# SCH_pls_work_not_lose_2022-07-18.net
KiCad netlist of a schematic drawn in EasyEDA
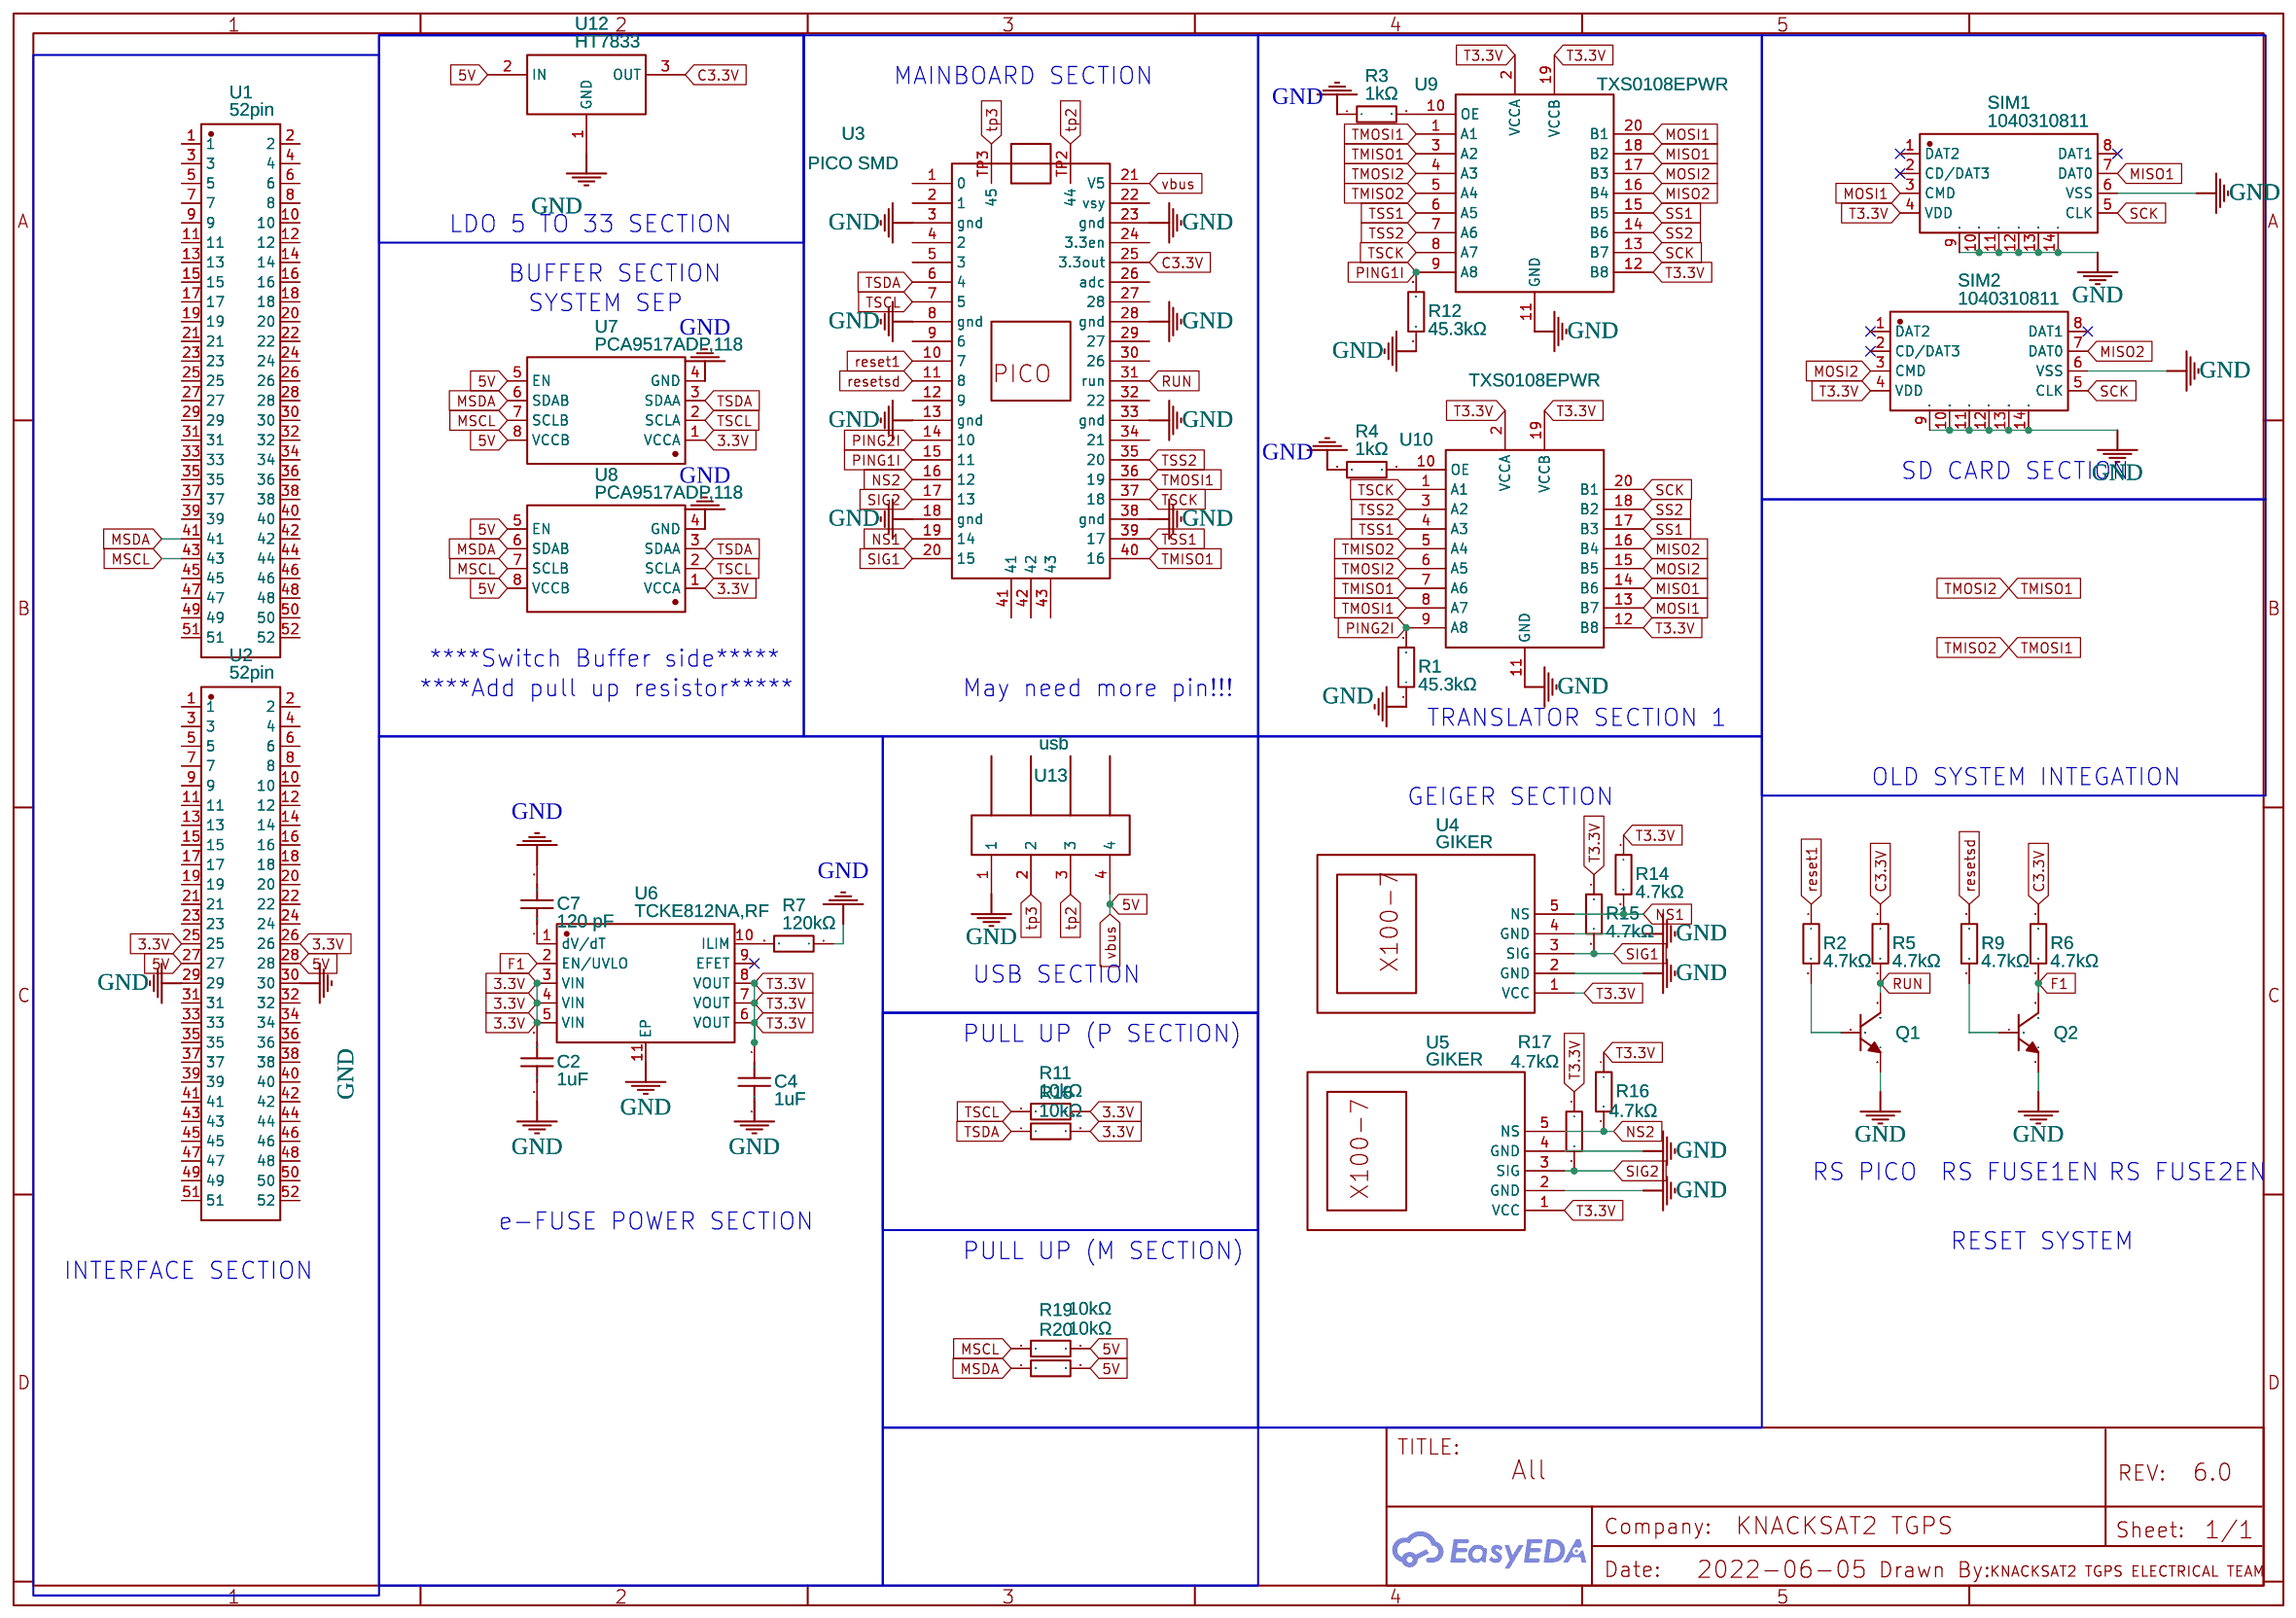
[diagram p0: schematic sheet]

(export (version "E")
  (design (tool "Eeschema 10.0.6"))
  (components
    (comp (ref "C2") (value "1uF") (libsource (lib "") (part "C_0603_US")))
    (comp (ref "C4") (value "1uF") (libsource (lib "") (part "C_0603_US")))
    (comp (ref "C7") (value "120 pF") (libsource (lib "") (part "C_0603_US")))
    (comp (ref "Q1")
      (value "2SC3324-BL(TE85L,F")
      (fields (field (name "BOM_Supplier Part") "C2999171"))
      (libsource (lib "") (part "2SC3324-BL(TE85L,F"))
    )
    (comp (ref "Q2")
      (value "2SC3324-BL(TE85L,F")
      (fields (field (name "BOM_Supplier Part") "C2999171"))
      (libsource (lib "") (part "2SC3324-BL(TE85L,F"))
    )
    (comp (ref "R1")
      (value "45.3kΩ")
      (fields
        (field (name "BOM_Manufacturer Part") "RMC040245.3K1%N")
        (field (name "BOM_Supplier Part") "C325554")
      )
      (libsource (lib "") (part "RMC040245.3K1%N"))
    )
    (comp (ref "R2")
      (value "4.7kΩ")
      (fields
        (field (name "BOM_Manufacturer Part") "RMC08054.7K1%N")
        (field (name "BOM_Supplier Part") "C269746")
      )
      (libsource (lib "") (part "RMC08054.7K1%N"))
    )
    (comp (ref "R3")
      (value "1kΩ")
      (fields
        (field (name "BOM_Manufacturer Part") "PTFR0805B1K00N9")
        (field (name "BOM_Supplier Part") "C328437")
      )
      (libsource (lib "") (part "PTFR0805B1K00N9"))
    )
    (comp (ref "R4")
      (value "1kΩ")
      (fields
        (field (name "BOM_Manufacturer Part") "PTFR0805B1K00N9")
        (field (name "BOM_Supplier Part") "C328437")
      )
      (libsource (lib "") (part "PTFR0805B1K00N9"))
    )
    (comp (ref "R5")
      (value "4.7kΩ")
      (fields
        (field (name "BOM_Manufacturer Part") "RMC08054.7K1%N")
        (field (name "BOM_Supplier Part") "C269746")
      )
      (libsource (lib "") (part "RMC08054.7K1%N"))
    )
    (comp (ref "R6")
      (value "4.7kΩ")
      (fields
        (field (name "BOM_Manufacturer Part") "RMC08054.7K1%N")
        (field (name "BOM_Supplier Part") "C269746")
      )
      (libsource (lib "") (part "RMC08054.7K1%N"))
    )
    (comp (ref "R7")
      (value "120kΩ")
      (fields
        (field (name "BOM_Manufacturer Part") "RMC0402120K1%N")
        (field (name "BOM_Supplier Part") "C325558")
      )
      (libsource (lib "") (part "RMC0402120K1%N"))
    )
    (comp (ref "R9")
      (value "4.7kΩ")
      (fields
        (field (name "BOM_Manufacturer Part") "RMC08054.7K1%N")
        (field (name "BOM_Supplier Part") "C269746")
      )
      (libsource (lib "") (part "RMC08054.7K1%N"))
    )
    (comp (ref "R11")
      (value "10kΩ")
      (fields
        (field (name "BOM_Manufacturer Part") "AECR0805F10K0K9")
        (field (name "BOM_Supplier Part") "C328381")
      )
      (libsource (lib "") (part "AECR0805F10K0K9"))
    )
    (comp (ref "R12")
      (value "45.3kΩ")
      (fields
        (field (name "BOM_Manufacturer Part") "RMC040245.3K1%N")
        (field (name "BOM_Supplier Part") "C325554")
      )
      (libsource (lib "") (part "RMC040245.3K1%N"))
    )
    (comp (ref "R14")
      (value "4.7kΩ")
      (fields
        (field (name "BOM_Manufacturer Part") "RMC08054.7K1%N")
        (field (name "BOM_Supplier Part") "C269746")
      )
      (libsource (lib "") (part "RMC08054.7K1%N"))
    )
    (comp (ref "R15")
      (value "4.7kΩ")
      (fields
        (field (name "BOM_Manufacturer Part") "RMC08054.7K1%N")
        (field (name "BOM_Supplier Part") "C269746")
      )
      (libsource (lib "") (part "RMC08054.7K1%N"))
    )
    (comp (ref "R16")
      (value "4.7kΩ")
      (fields
        (field (name "BOM_Manufacturer Part") "RMC08054.7K1%N")
        (field (name "BOM_Supplier Part") "C269746")
      )
      (libsource (lib "") (part "RMC08054.7K1%N"))
    )
    (comp (ref "R17")
      (value "4.7kΩ")
      (fields
        (field (name "BOM_Manufacturer Part") "RMC08054.7K1%N")
        (field (name "BOM_Supplier Part") "C269746")
      )
      (libsource (lib "") (part "RMC08054.7K1%N"))
    )
    (comp (ref "R18")
      (value "10kΩ")
      (fields
        (field (name "BOM_Manufacturer Part") "AECR0805F10K0K9")
        (field (name "BOM_Supplier Part") "C328381")
      )
      (libsource (lib "") (part "AECR0805F10K0K9"))
    )
    (comp (ref "R19")
      (value "10kΩ")
      (fields
        (field (name "BOM_Manufacturer Part") "AECR0805F10K0K9")
        (field (name "BOM_Supplier Part") "C328381")
      )
      (libsource (lib "") (part "AECR0805F10K0K9"))
    )
    (comp (ref "R20")
      (value "10kΩ")
      (fields
        (field (name "BOM_Manufacturer Part") "AECR0805F10K0K9")
        (field (name "BOM_Supplier Part") "C328381")
      )
      (libsource (lib "") (part "AECR0805F10K0K9"))
    )
    (comp (ref "SIM1")
      (value "1040310811")
      (fields (field (name "BOM_Supplier Part") "C585350"))
      (libsource (lib "") (part "1040310811"))
    )
    (comp (ref "SIM2")
      (value "1040310811")
      (fields (field (name "BOM_Supplier Part") "C585350"))
      (libsource (lib "") (part "1040310811"))
    )
    (comp (ref "U1") (value "52pin") (libsource (lib "") (part "52pin")))
    (comp (ref "U2") (value "52pin") (libsource (lib "") (part "52pin")))
    (comp (ref "U3") (value "PICO SMD") (libsource (lib "") (part "PICO SMD")))
    (comp (ref "U4") (value "GIKER") (libsource (lib "") (part "GIKER")))
    (comp (ref "U5") (value "GIKER") (libsource (lib "") (part "GIKER_1")))
    (comp (ref "U6")
      (value "TCKE812NA,RF")
      (fields (field (name "BOM_Supplier Part") "C1880271"))
      (libsource (lib "") (part "TCKE812NA,RF"))
    )
    (comp (ref "U7")
      (value "PCA9517ADP,118")
      (fields (field (name "BOM_Supplier Part") "C80799"))
      (libsource (lib "") (part "PCA9517ADP,118"))
    )
    (comp (ref "U8")
      (value "PCA9517ADP,118")
      (fields (field (name "BOM_Supplier Part") "C80799"))
      (libsource (lib "") (part "PCA9517ADP,118"))
    )
    (comp (ref "U9")
      (value "TXS0108EPWR")
      (fields (field (name "BOM_Supplier Part") "C17206"))
      (libsource (lib "") (part "TXS0108EPWR"))
    )
    (comp (ref "U10")
      (value "TXS0108EPWR")
      (fields (field (name "BOM_Supplier Part") "C17206"))
      (libsource (lib "") (part "TXS0108EPWR"))
    )
    (comp (ref "U12")
      (value "HT7833")
      (fields (field (name "BOM_Supplier Part") "C50936"))
      (libsource (lib "") (part "HT7833"))
    )
    (comp (ref "U13") (value "usb") (libsource (lib "") (part "usb")))
  )
  (nets
    (net (code "1") (name "3.3V") (class "Default")
      (node (ref "C2") (pin "2") (pinfunction "2_2") (pintype "unspecified"))
      (node (ref "R11") (pin "2") (pinfunction "2_2") (pintype "unspecified"))
      (node (ref "R18") (pin "2") (pinfunction "2_2") (pintype "unspecified"))
      (node (ref "U2") (pin "25") (pinfunction "25_25") (pintype "unspecified"))
      (node (ref "U2") (pin "26") (pinfunction "26_26") (pintype "unspecified"))
      (node (ref "U6") (pin "3") (pinfunction "VIN_3") (pintype "unspecified"))
      (node (ref "U6") (pin "4") (pinfunction "VIN_4") (pintype "unspecified"))
      (node (ref "U6") (pin "5") (pinfunction "VIN_5") (pintype "unspecified"))
      (node (ref "U7") (pin "1") (pinfunction "VCCA_1") (pintype "unspecified"))
      (node (ref "U8") (pin "1") (pinfunction "VCCA_1") (pintype "unspecified"))
    )
    (net (code "2") (name "5V") (class "Default")
      (node (ref "R19") (pin "2") (pinfunction "2_2") (pintype "unspecified"))
      (node (ref "R20") (pin "2") (pinfunction "2_2") (pintype "unspecified"))
      (node (ref "U12") (pin "2") (pinfunction "IN_2") (pintype "passive"))
      (node (ref "U13") (pin "4") (pinfunction "4_4") (pintype "unspecified"))
      (node (ref "U2") (pin "27") (pinfunction "27_27") (pintype "unspecified"))
      (node (ref "U2") (pin "28") (pinfunction "28_28") (pintype "unspecified"))
      (node (ref "U3") (pin "21") (pinfunction "V5_21") (pintype "unspecified"))
      (node (ref "U7") (pin "5") (pinfunction "EN_5") (pintype "unspecified"))
      (node (ref "U7") (pin "8") (pinfunction "VCCB_8") (pintype "unspecified"))
      (node (ref "U8") (pin "5") (pinfunction "EN_5") (pintype "unspecified"))
      (node (ref "U8") (pin "8") (pinfunction "VCCB_8") (pintype "unspecified"))
    )
    (net (code "3") (name "C3.3V") (class "Default")
      (node (ref "R5") (pin "1") (pinfunction "1_1") (pintype "unspecified"))
      (node (ref "R6") (pin "1") (pinfunction "1_1") (pintype "unspecified"))
      (node (ref "U12") (pin "3") (pinfunction "OUT_3") (pintype "passive"))
      (node (ref "U3") (pin "25") (pinfunction "3.3out_25") (pintype "unspecified"))
    )
    (net (code "4") (name "F1") (class "Default")
      (node (ref "Q2") (pin "3") (pinfunction "C_3") (pintype "unspecified"))
      (node (ref "R6") (pin "2") (pinfunction "2_2") (pintype "unspecified"))
      (node (ref "U6") (pin "2") (pinfunction "EN/UVLO_2") (pintype "unspecified"))
    )
    (net (code "5") (name "GND") (class "Default")
      (node (ref "C2") (pin "1") (pinfunction "1_1") (pintype "unspecified"))
      (node (ref "C4") (pin "1") (pinfunction "1_1") (pintype "unspecified"))
      (node (ref "C7") (pin "2") (pinfunction "2_2") (pintype "unspecified"))
      (node (ref "Q1") (pin "2") (pinfunction "E_2") (pintype "unspecified"))
      (node (ref "Q2") (pin "2") (pinfunction "E_2") (pintype "unspecified"))
      (node (ref "R1") (pin "1") (pinfunction "1_1") (pintype "unspecified"))
      (node (ref "R12") (pin "1") (pinfunction "1_1") (pintype "unspecified"))
      (node (ref "R3") (pin "1") (pinfunction "1_1") (pintype "unspecified"))
      (node (ref "R4") (pin "1") (pinfunction "1_1") (pintype "unspecified"))
      (node (ref "R7") (pin "1") (pinfunction "1_1") (pintype "unspecified"))
      (node (ref "SIM1") (pin "10") (pinfunction "10_10") (pintype "unspecified"))
      (node (ref "SIM1") (pin "11") (pinfunction "11_11") (pintype "unspecified"))
      (node (ref "SIM1") (pin "12") (pinfunction "12_12") (pintype "unspecified"))
      (node (ref "SIM1") (pin "13") (pinfunction "13_13") (pintype "unspecified"))
      (node (ref "SIM1") (pin "14") (pinfunction "14_14") (pintype "unspecified"))
      (node (ref "SIM1") (pin "6") (pinfunction "VSS_6") (pintype "unspecified"))
      (node (ref "SIM1") (pin "9") (pinfunction "9_9") (pintype "unspecified"))
      (node (ref "SIM2") (pin "10") (pinfunction "10_10") (pintype "unspecified"))
      (node (ref "SIM2") (pin "11") (pinfunction "11_11") (pintype "unspecified"))
      (node (ref "SIM2") (pin "12") (pinfunction "12_12") (pintype "unspecified"))
      (node (ref "SIM2") (pin "13") (pinfunction "13_13") (pintype "unspecified"))
      (node (ref "SIM2") (pin "14") (pinfunction "14_14") (pintype "unspecified"))
      (node (ref "SIM2") (pin "6") (pinfunction "VSS_6") (pintype "unspecified"))
      (node (ref "SIM2") (pin "9") (pinfunction "9_9") (pintype "unspecified"))
      (node (ref "U10") (pin "11") (pinfunction "GND_11") (pintype "unspecified"))
      (node (ref "U12") (pin "1") (pinfunction "GND_1") (pintype "passive"))
      (node (ref "U13") (pin "1") (pinfunction "1_1") (pintype "unspecified"))
      (node (ref "U2") (pin "29") (pinfunction "29_29") (pintype "unspecified"))
      (node (ref "U2") (pin "30") (pinfunction "30_30") (pintype "unspecified"))
      (node (ref "U3") (pin "13") (pinfunction "gnd_13") (pintype "unspecified"))
      (node (ref "U3") (pin "18") (pinfunction "gnd_18") (pintype "unspecified"))
      (node (ref "U3") (pin "23") (pinfunction "gnd_23") (pintype "unspecified"))
      (node (ref "U3") (pin "28") (pinfunction "gnd_28") (pintype "unspecified"))
      (node (ref "U3") (pin "3") (pinfunction "gnd_3") (pintype "unspecified"))
      (node (ref "U3") (pin "33") (pinfunction "gnd_33") (pintype "unspecified"))
      (node (ref "U3") (pin "38") (pinfunction "gnd_38") (pintype "unspecified"))
      (node (ref "U3") (pin "8") (pinfunction "gnd_8") (pintype "unspecified"))
      (node (ref "U4") (pin "2") (pinfunction "GND_2") (pintype "unspecified"))
      (node (ref "U4") (pin "4") (pinfunction "GND_4") (pintype "unspecified"))
      (node (ref "U5") (pin "2") (pinfunction "GND_2") (pintype "unspecified"))
      (node (ref "U5") (pin "4") (pinfunction "GND_4") (pintype "unspecified"))
      (node (ref "U6") (pin "11") (pinfunction "EP_11") (pintype "unspecified"))
      (node (ref "U7") (pin "4") (pinfunction "GND_4") (pintype "unspecified"))
      (node (ref "U8") (pin "4") (pinfunction "GND_4") (pintype "unspecified"))
      (node (ref "U9") (pin "11") (pinfunction "GND_11") (pintype "unspecified"))
    )
    (net (code "6") (name "MISO1") (class "Default")
      (node (ref "SIM1") (pin "7") (pinfunction "DAT0_7") (pintype "unspecified"))
      (node (ref "U10") (pin "14") (pinfunction "B6_14") (pintype "unspecified"))
      (node (ref "U9") (pin "18") (pinfunction "B2_18") (pintype "unspecified"))
    )
    (net (code "7") (name "MISO2") (class "Default")
      (node (ref "SIM2") (pin "7") (pinfunction "DAT0_7") (pintype "unspecified"))
      (node (ref "U10") (pin "16") (pinfunction "B4_16") (pintype "unspecified"))
      (node (ref "U9") (pin "16") (pinfunction "B4_16") (pintype "unspecified"))
    )
    (net (code "8") (name "MOSI1") (class "Default")
      (node (ref "SIM1") (pin "3") (pinfunction "CMD_3") (pintype "unspecified"))
      (node (ref "U10") (pin "13") (pinfunction "B7_13") (pintype "unspecified"))
      (node (ref "U9") (pin "20") (pinfunction "B1_20") (pintype "unspecified"))
    )
    (net (code "9") (name "MOSI2") (class "Default")
      (node (ref "SIM2") (pin "3") (pinfunction "CMD_3") (pintype "unspecified"))
      (node (ref "U10") (pin "15") (pinfunction "B5_15") (pintype "unspecified"))
      (node (ref "U9") (pin "17") (pinfunction "B3_17") (pintype "unspecified"))
    )
    (net (code "10") (name "MSCL") (class "Default")
      (node (ref "R19") (pin "1") (pinfunction "1_1") (pintype "unspecified"))
      (node (ref "U1") (pin "43") (pinfunction "43_43") (pintype "unspecified"))
      (node (ref "U7") (pin "7") (pinfunction "SCLB_7") (pintype "unspecified"))
      (node (ref "U8") (pin "7") (pinfunction "SCLB_7") (pintype "unspecified"))
    )
    (net (code "11") (name "MSDA") (class "Default")
      (node (ref "R20") (pin "1") (pinfunction "1_1") (pintype "unspecified"))
      (node (ref "U1") (pin "41") (pinfunction "41_41") (pintype "unspecified"))
      (node (ref "U7") (pin "6") (pinfunction "SDAB_6") (pintype "unspecified"))
      (node (ref "U8") (pin "6") (pinfunction "SDAB_6") (pintype "unspecified"))
    )
    (net (code "12") (name "NS1") (class "Default")
      (node (ref "R14") (pin "2") (pinfunction "2_2") (pintype "unspecified"))
      (node (ref "U3") (pin "19") (pinfunction "14_19") (pintype "unspecified"))
      (node (ref "U4") (pin "5") (pinfunction "NS_5") (pintype "unspecified"))
    )
    (net (code "13") (name "NS2") (class "Default")
      (node (ref "R16") (pin "2") (pinfunction "2_2") (pintype "unspecified"))
      (node (ref "U3") (pin "16") (pinfunction "12_16") (pintype "unspecified"))
      (node (ref "U5") (pin "5") (pinfunction "NS_5") (pintype "unspecified"))
    )
    (net (code "14") (name "Net-(Q1-B)") (class "Default")
      (node (ref "Q1") (pin "1") (pinfunction "B_1") (pintype "unspecified"))
      (node (ref "R2") (pin "2") (pinfunction "2_2") (pintype "unspecified"))
    )
    (net (code "15") (name "Net-(Q2-B)") (class "Default")
      (node (ref "Q2") (pin "1") (pinfunction "B_1") (pintype "unspecified"))
      (node (ref "R9") (pin "2") (pinfunction "2_2") (pintype "unspecified"))
    )
    (net (code "16") (name "Net-(U6-ILIM)") (class "Default")
      (node (ref "R7") (pin "2") (pinfunction "2_2") (pintype "unspecified"))
      (node (ref "U6") (pin "10") (pinfunction "ILIM_10") (pintype "unspecified"))
    )
    (net (code "17") (name "Net-(U6-dV{slash}dT)") (class "Default")
      (node (ref "C7") (pin "1") (pinfunction "1_1") (pintype "unspecified"))
      (node (ref "U6") (pin "1") (pinfunction "dV/dT_1") (pintype "unspecified"))
    )
    (net (code "18") (name "Net-(U9-OE)") (class "Default")
      (node (ref "R3") (pin "2") (pinfunction "2_2") (pintype "unspecified"))
      (node (ref "U9") (pin "10") (pinfunction "OE_10") (pintype "unspecified"))
    )
    (net (code "19") (name "Net-(U10-OE)") (class "Default")
      (node (ref "R4") (pin "2") (pinfunction "2_2") (pintype "unspecified"))
      (node (ref "U10") (pin "10") (pinfunction "OE_10") (pintype "unspecified"))
    )
    (net (code "20") (name "PING1I") (class "Default")
      (node (ref "R12") (pin "2") (pinfunction "2_2") (pintype "unspecified"))
      (node (ref "U3") (pin "15") (pinfunction "11_15") (pintype "unspecified"))
      (node (ref "U9") (pin "9") (pinfunction "A8_9") (pintype "unspecified"))
    )
    (net (code "21") (name "PING2I") (class "Default")
      (node (ref "R1") (pin "2") (pinfunction "2_2") (pintype "unspecified"))
      (node (ref "U10") (pin "9") (pinfunction "A8_9") (pintype "unspecified"))
      (node (ref "U3") (pin "14") (pinfunction "10_14") (pintype "unspecified"))
    )
    (net (code "22") (name "RUN") (class "Default")
      (node (ref "Q1") (pin "3") (pinfunction "C_3") (pintype "unspecified"))
      (node (ref "R5") (pin "2") (pinfunction "2_2") (pintype "unspecified"))
      (node (ref "U3") (pin "31") (pinfunction "run_31") (pintype "unspecified"))
    )
    (net (code "23") (name "SCK") (class "Default")
      (node (ref "SIM1") (pin "5") (pinfunction "CLK_5") (pintype "unspecified"))
      (node (ref "SIM2") (pin "5") (pinfunction "CLK_5") (pintype "unspecified"))
      (node (ref "U10") (pin "20") (pinfunction "B1_20") (pintype "unspecified"))
      (node (ref "U9") (pin "13") (pinfunction "B7_13") (pintype "unspecified"))
    )
    (net (code "24") (name "SIG1") (class "Default")
      (node (ref "R15") (pin "2") (pinfunction "2_2") (pintype "unspecified"))
      (node (ref "U3") (pin "20") (pinfunction "15_20") (pintype "unspecified"))
      (node (ref "U4") (pin "3") (pinfunction "SIG_3") (pintype "unspecified"))
    )
    (net (code "25") (name "SIG2") (class "Default")
      (node (ref "R17") (pin "2") (pinfunction "2_2") (pintype "unspecified"))
      (node (ref "U3") (pin "17") (pinfunction "13_17") (pintype "unspecified"))
      (node (ref "U5") (pin "3") (pinfunction "SIG_3") (pintype "unspecified"))
    )
    (net (code "26") (name "SS1") (class "Default")
      (node (ref "U10") (pin "17") (pinfunction "B3_17") (pintype "unspecified"))
      (node (ref "U9") (pin "15") (pinfunction "B5_15") (pintype "unspecified"))
    )
    (net (code "27") (name "SS2") (class "Default")
      (node (ref "U10") (pin "18") (pinfunction "B2_18") (pintype "unspecified"))
      (node (ref "U9") (pin "14") (pinfunction "B6_14") (pintype "unspecified"))
    )
    (net (code "28") (name "T3.3V") (class "Default")
      (node (ref "C4") (pin "2") (pinfunction "2_2") (pintype "unspecified"))
      (node (ref "R14") (pin "1") (pinfunction "1_1") (pintype "unspecified"))
      (node (ref "R15") (pin "1") (pinfunction "1_1") (pintype "unspecified"))
      (node (ref "R16") (pin "1") (pinfunction "1_1") (pintype "unspecified"))
      (node (ref "R17") (pin "1") (pinfunction "1_1") (pintype "unspecified"))
      (node (ref "SIM1") (pin "4") (pinfunction "VDD_4") (pintype "unspecified"))
      (node (ref "SIM2") (pin "4") (pinfunction "VDD_4") (pintype "unspecified"))
      (node (ref "U10") (pin "12") (pinfunction "B8_12") (pintype "unspecified"))
      (node (ref "U10") (pin "19") (pinfunction "VCCB_19") (pintype "unspecified"))
      (node (ref "U10") (pin "2") (pinfunction "VCCA_2") (pintype "unspecified"))
      (node (ref "U4") (pin "1") (pinfunction "VCC_1") (pintype "unspecified"))
      (node (ref "U5") (pin "1") (pinfunction "VCC_1") (pintype "unspecified"))
      (node (ref "U6") (pin "6") (pinfunction "VOUT_6") (pintype "unspecified"))
      (node (ref "U6") (pin "7") (pinfunction "VOUT_7") (pintype "unspecified"))
      (node (ref "U6") (pin "8") (pinfunction "VOUT_8") (pintype "unspecified"))
      (node (ref "U9") (pin "12") (pinfunction "B8_12") (pintype "unspecified"))
      (node (ref "U9") (pin "19") (pinfunction "VCCB_19") (pintype "unspecified"))
      (node (ref "U9") (pin "2") (pinfunction "VCCA_2") (pintype "unspecified"))
    )
    (net (code "29") (name "TMISO1") (class "Default")
      (node (ref "U10") (pin "6") (pinfunction "A5_6") (pintype "unspecified"))
      (node (ref "U10") (pin "7") (pinfunction "A6_7") (pintype "unspecified"))
      (node (ref "U3") (pin "40") (pinfunction "16_40") (pintype "unspecified"))
      (node (ref "U9") (pin "3") (pinfunction "A2_3") (pintype "unspecified"))
      (node (ref "U9") (pin "4") (pinfunction "A3_4") (pintype "unspecified"))
    )
    (net (code "30") (name "TMISO2") (class "Default")
      (node (ref "U10") (pin "5") (pinfunction "A4_5") (pintype "unspecified"))
      (node (ref "U10") (pin "8") (pinfunction "A7_8") (pintype "unspecified"))
      (node (ref "U3") (pin "36") (pinfunction "19_36") (pintype "unspecified"))
      (node (ref "U9") (pin "1") (pinfunction "A1_1") (pintype "unspecified"))
      (node (ref "U9") (pin "5") (pinfunction "A4_5") (pintype "unspecified"))
    )
    (net (code "31") (name "TSCK") (class "Default")
      (node (ref "U10") (pin "1") (pinfunction "A1_1") (pintype "unspecified"))
      (node (ref "U3") (pin "37") (pinfunction "18_37") (pintype "unspecified"))
      (node (ref "U9") (pin "8") (pinfunction "A7_8") (pintype "unspecified"))
    )
    (net (code "32") (name "TSCL") (class "Default")
      (node (ref "R11") (pin "1") (pinfunction "1_1") (pintype "unspecified"))
      (node (ref "U3") (pin "7") (pinfunction "5_7") (pintype "unspecified"))
      (node (ref "U7") (pin "2") (pinfunction "SCLA_2") (pintype "unspecified"))
      (node (ref "U8") (pin "2") (pinfunction "SCLA_2") (pintype "unspecified"))
    )
    (net (code "33") (name "TSDA") (class "Default")
      (node (ref "R18") (pin "1") (pinfunction "1_1") (pintype "unspecified"))
      (node (ref "U3") (pin "6") (pinfunction "4_6") (pintype "unspecified"))
      (node (ref "U7") (pin "3") (pinfunction "SDAA_3") (pintype "unspecified"))
      (node (ref "U8") (pin "3") (pinfunction "SDAA_3") (pintype "unspecified"))
    )
    (net (code "34") (name "TSS1") (class "Default")
      (node (ref "U10") (pin "4") (pinfunction "A3_4") (pintype "unspecified"))
      (node (ref "U3") (pin "39") (pinfunction "17_39") (pintype "unspecified"))
      (node (ref "U9") (pin "6") (pinfunction "A5_6") (pintype "unspecified"))
    )
    (net (code "35") (name "TSS2") (class "Default")
      (node (ref "U10") (pin "3") (pinfunction "A2_3") (pintype "unspecified"))
      (node (ref "U3") (pin "35") (pinfunction "20_35") (pintype "unspecified"))
      (node (ref "U9") (pin "7") (pinfunction "A6_7") (pintype "unspecified"))
    )
    (net (code "36") (name "reset1") (class "Default")
      (node (ref "R2") (pin "1") (pinfunction "1_1") (pintype "unspecified"))
      (node (ref "U3") (pin "10") (pinfunction "7_10") (pintype "unspecified"))
    )
    (net (code "37") (name "resetsd") (class "Default")
      (node (ref "R9") (pin "1") (pinfunction "1_1") (pintype "unspecified"))
      (node (ref "U3") (pin "11") (pinfunction "8_11") (pintype "unspecified"))
    )
    (net (code "38") (name "tp2") (class "Default")
      (node (ref "U13") (pin "3") (pinfunction "3_3") (pintype "unspecified"))
      (node (ref "U3") (pin "TP2") (pinfunction "44_TP2") (pintype "unspecified"))
    )
    (net (code "39") (name "tp3") (class "Default")
      (node (ref "U13") (pin "2") (pinfunction "2_2") (pintype "unspecified"))
      (node (ref "U3") (pin "TP3") (pinfunction "45_TP3") (pintype "unspecified"))
    )
    (net (code "40") (name "unconnected-(SIM1-CD{slash}DAT3-Pad2)") (class "Default")
      (node (ref "SIM1") (pin "2") (pinfunction "CD/DAT3_2") (pintype "unspecified+no_connect"))
    )
    (net (code "41") (name "unconnected-(SIM1-DAT1-Pad8)") (class "Default")
      (node (ref "SIM1") (pin "8") (pinfunction "DAT1_8") (pintype "unspecified+no_connect"))
    )
    (net (code "42") (name "unconnected-(SIM1-DAT2-Pad1)") (class "Default")
      (node (ref "SIM1") (pin "1") (pinfunction "DAT2_1") (pintype "unspecified+no_connect"))
    )
    (net (code "43") (name "unconnected-(SIM2-CD{slash}DAT3-Pad2)") (class "Default")
      (node (ref "SIM2") (pin "2") (pinfunction "CD/DAT3_2") (pintype "unspecified+no_connect"))
    )
    (net (code "44") (name "unconnected-(SIM2-DAT1-Pad8)") (class "Default")
      (node (ref "SIM2") (pin "8") (pinfunction "DAT1_8") (pintype "unspecified+no_connect"))
    )
    (net (code "45") (name "unconnected-(SIM2-DAT2-Pad1)") (class "Default")
      (node (ref "SIM2") (pin "1") (pinfunction "DAT2_1") (pintype "unspecified+no_connect"))
    )
    (net (code "46") (name "unconnected-(U1-Pad1)") (class "Default")
      (node (ref "U1") (pin "1") (pinfunction "1_1") (pintype "unspecified"))
    )
    (net (code "47") (name "unconnected-(U1-Pad2)") (class "Default")
      (node (ref "U1") (pin "2") (pinfunction "2_2") (pintype "unspecified"))
    )
    (net (code "48") (name "unconnected-(U1-Pad3)") (class "Default")
      (node (ref "U1") (pin "3") (pinfunction "3_3") (pintype "unspecified"))
    )
    (net (code "49") (name "unconnected-(U1-Pad4)") (class "Default")
      (node (ref "U1") (pin "4") (pinfunction "4_4") (pintype "unspecified"))
    )
    (net (code "50") (name "unconnected-(U1-Pad5)") (class "Default")
      (node (ref "U1") (pin "5") (pinfunction "5_5") (pintype "unspecified"))
    )
    (net (code "51") (name "unconnected-(U1-Pad6)") (class "Default")
      (node (ref "U1") (pin "6") (pinfunction "6_6") (pintype "unspecified"))
    )
    (net (code "52") (name "unconnected-(U1-Pad7)") (class "Default")
      (node (ref "U1") (pin "7") (pinfunction "7_7") (pintype "unspecified"))
    )
    (net (code "53") (name "unconnected-(U1-Pad8)") (class "Default")
      (node (ref "U1") (pin "8") (pinfunction "8_8") (pintype "unspecified"))
    )
    (net (code "54") (name "unconnected-(U1-Pad9)") (class "Default")
      (node (ref "U1") (pin "9") (pinfunction "9_9") (pintype "unspecified"))
    )
    (net (code "55") (name "unconnected-(U1-Pad10)") (class "Default")
      (node (ref "U1") (pin "10") (pinfunction "10_10") (pintype "unspecified"))
    )
    (net (code "56") (name "unconnected-(U1-Pad11)") (class "Default")
      (node (ref "U1") (pin "11") (pinfunction "11_11") (pintype "unspecified"))
    )
    (net (code "57") (name "unconnected-(U1-Pad12)") (class "Default")
      (node (ref "U1") (pin "12") (pinfunction "12_12") (pintype "unspecified"))
    )
    (net (code "58") (name "unconnected-(U1-Pad13)") (class "Default")
      (node (ref "U1") (pin "13") (pinfunction "13_13") (pintype "unspecified"))
    )
    (net (code "59") (name "unconnected-(U1-Pad14)") (class "Default")
      (node (ref "U1") (pin "14") (pinfunction "14_14") (pintype "unspecified"))
    )
    (net (code "60") (name "unconnected-(U1-Pad15)") (class "Default")
      (node (ref "U1") (pin "15") (pinfunction "15_15") (pintype "unspecified"))
    )
    (net (code "61") (name "unconnected-(U1-Pad16)") (class "Default")
      (node (ref "U1") (pin "16") (pinfunction "16_16") (pintype "unspecified"))
    )
    (net (code "62") (name "unconnected-(U1-Pad17)") (class "Default")
      (node (ref "U1") (pin "17") (pinfunction "17_17") (pintype "unspecified"))
    )
    (net (code "63") (name "unconnected-(U1-Pad18)") (class "Default")
      (node (ref "U1") (pin "18") (pinfunction "18_18") (pintype "unspecified"))
    )
    (net (code "64") (name "unconnected-(U1-Pad19)") (class "Default")
      (node (ref "U1") (pin "19") (pinfunction "19_19") (pintype "unspecified"))
    )
    (net (code "65") (name "unconnected-(U1-Pad20)") (class "Default")
      (node (ref "U1") (pin "20") (pinfunction "20_20") (pintype "unspecified"))
    )
    (net (code "66") (name "unconnected-(U1-Pad21)") (class "Default")
      (node (ref "U1") (pin "21") (pinfunction "21_21") (pintype "unspecified"))
    )
    (net (code "67") (name "unconnected-(U1-Pad22)") (class "Default")
      (node (ref "U1") (pin "22") (pinfunction "22_22") (pintype "unspecified"))
    )
    (net (code "68") (name "unconnected-(U1-Pad23)") (class "Default")
      (node (ref "U1") (pin "23") (pinfunction "23_23") (pintype "unspecified"))
    )
    (net (code "69") (name "unconnected-(U1-Pad24)") (class "Default")
      (node (ref "U1") (pin "24") (pinfunction "24_24") (pintype "unspecified"))
    )
    (net (code "70") (name "unconnected-(U1-Pad25)") (class "Default")
      (node (ref "U1") (pin "25") (pinfunction "25_25") (pintype "unspecified"))
    )
    (net (code "71") (name "unconnected-(U1-Pad26)") (class "Default")
      (node (ref "U1") (pin "26") (pinfunction "26_26") (pintype "unspecified"))
    )
    (net (code "72") (name "unconnected-(U1-Pad27)") (class "Default")
      (node (ref "U1") (pin "27") (pinfunction "27_27") (pintype "unspecified"))
    )
    (net (code "73") (name "unconnected-(U1-Pad28)") (class "Default")
      (node (ref "U1") (pin "28") (pinfunction "28_28") (pintype "unspecified"))
    )
    (net (code "74") (name "unconnected-(U1-Pad29)") (class "Default")
      (node (ref "U1") (pin "29") (pinfunction "29_29") (pintype "unspecified"))
    )
    (net (code "75") (name "unconnected-(U1-Pad30)") (class "Default")
      (node (ref "U1") (pin "30") (pinfunction "30_30") (pintype "unspecified"))
    )
    (net (code "76") (name "unconnected-(U1-Pad31)") (class "Default")
      (node (ref "U1") (pin "31") (pinfunction "31_31") (pintype "unspecified"))
    )
    (net (code "77") (name "unconnected-(U1-Pad32)") (class "Default")
      (node (ref "U1") (pin "32") (pinfunction "32_32") (pintype "unspecified"))
    )
    (net (code "78") (name "unconnected-(U1-Pad33)") (class "Default")
      (node (ref "U1") (pin "33") (pinfunction "33_33") (pintype "unspecified"))
    )
    (net (code "79") (name "unconnected-(U1-Pad34)") (class "Default")
      (node (ref "U1") (pin "34") (pinfunction "34_34") (pintype "unspecified"))
    )
    (net (code "80") (name "unconnected-(U1-Pad35)") (class "Default")
      (node (ref "U1") (pin "35") (pinfunction "35_35") (pintype "unspecified"))
    )
    (net (code "81") (name "unconnected-(U1-Pad36)") (class "Default")
      (node (ref "U1") (pin "36") (pinfunction "36_36") (pintype "unspecified"))
    )
    (net (code "82") (name "unconnected-(U1-Pad37)") (class "Default")
      (node (ref "U1") (pin "37") (pinfunction "37_37") (pintype "unspecified"))
    )
    (net (code "83") (name "unconnected-(U1-Pad38)") (class "Default")
      (node (ref "U1") (pin "38") (pinfunction "38_38") (pintype "unspecified"))
    )
    (net (code "84") (name "unconnected-(U1-Pad39)") (class "Default")
      (node (ref "U1") (pin "39") (pinfunction "39_39") (pintype "unspecified"))
    )
    (net (code "85") (name "unconnected-(U1-Pad40)") (class "Default")
      (node (ref "U1") (pin "40") (pinfunction "40_40") (pintype "unspecified"))
    )
    (net (code "86") (name "unconnected-(U1-Pad42)") (class "Default")
      (node (ref "U1") (pin "42") (pinfunction "42_42") (pintype "unspecified"))
    )
    (net (code "87") (name "unconnected-(U1-Pad44)") (class "Default")
      (node (ref "U1") (pin "44") (pinfunction "44_44") (pintype "unspecified"))
    )
    (net (code "88") (name "unconnected-(U1-Pad45)") (class "Default")
      (node (ref "U1") (pin "45") (pinfunction "45_45") (pintype "unspecified"))
    )
    (net (code "89") (name "unconnected-(U1-Pad46)") (class "Default")
      (node (ref "U1") (pin "46") (pinfunction "46_46") (pintype "unspecified"))
    )
    (net (code "90") (name "unconnected-(U1-Pad47)") (class "Default")
      (node (ref "U1") (pin "47") (pinfunction "47_47") (pintype "unspecified"))
    )
    (net (code "91") (name "unconnected-(U1-Pad48)") (class "Default")
      (node (ref "U1") (pin "48") (pinfunction "48_48") (pintype "unspecified"))
    )
    (net (code "92") (name "unconnected-(U1-Pad49)") (class "Default")
      (node (ref "U1") (pin "49") (pinfunction "49_49") (pintype "unspecified"))
    )
    (net (code "93") (name "unconnected-(U1-Pad50)") (class "Default")
      (node (ref "U1") (pin "50") (pinfunction "50_50") (pintype "unspecified"))
    )
    (net (code "94") (name "unconnected-(U1-Pad51)") (class "Default")
      (node (ref "U1") (pin "51") (pinfunction "51_51") (pintype "unspecified"))
    )
    (net (code "95") (name "unconnected-(U1-Pad52)") (class "Default")
      (node (ref "U1") (pin "52") (pinfunction "52_52") (pintype "unspecified"))
    )
    (net (code "96") (name "unconnected-(U2-Pad1)") (class "Default")
      (node (ref "U2") (pin "1") (pinfunction "1_1") (pintype "unspecified"))
    )
    (net (code "97") (name "unconnected-(U2-Pad2)") (class "Default")
      (node (ref "U2") (pin "2") (pinfunction "2_2") (pintype "unspecified"))
    )
    (net (code "98") (name "unconnected-(U2-Pad3)") (class "Default")
      (node (ref "U2") (pin "3") (pinfunction "3_3") (pintype "unspecified"))
    )
    (net (code "99") (name "unconnected-(U2-Pad4)") (class "Default")
      (node (ref "U2") (pin "4") (pinfunction "4_4") (pintype "unspecified"))
    )
    (net (code "100") (name "unconnected-(U2-Pad5)") (class "Default")
      (node (ref "U2") (pin "5") (pinfunction "5_5") (pintype "unspecified"))
    )
    (net (code "101") (name "unconnected-(U2-Pad6)") (class "Default")
      (node (ref "U2") (pin "6") (pinfunction "6_6") (pintype "unspecified"))
    )
    (net (code "102") (name "unconnected-(U2-Pad7)") (class "Default")
      (node (ref "U2") (pin "7") (pinfunction "7_7") (pintype "unspecified"))
    )
    (net (code "103") (name "unconnected-(U2-Pad8)") (class "Default")
      (node (ref "U2") (pin "8") (pinfunction "8_8") (pintype "unspecified"))
    )
    (net (code "104") (name "unconnected-(U2-Pad9)") (class "Default")
      (node (ref "U2") (pin "9") (pinfunction "9_9") (pintype "unspecified"))
    )
    (net (code "105") (name "unconnected-(U2-Pad10)") (class "Default")
      (node (ref "U2") (pin "10") (pinfunction "10_10") (pintype "unspecified"))
    )
    (net (code "106") (name "unconnected-(U2-Pad11)") (class "Default")
      (node (ref "U2") (pin "11") (pinfunction "11_11") (pintype "unspecified"))
    )
    (net (code "107") (name "unconnected-(U2-Pad12)") (class "Default")
      (node (ref "U2") (pin "12") (pinfunction "12_12") (pintype "unspecified"))
    )
    (net (code "108") (name "unconnected-(U2-Pad13)") (class "Default")
      (node (ref "U2") (pin "13") (pinfunction "13_13") (pintype "unspecified"))
    )
    (net (code "109") (name "unconnected-(U2-Pad14)") (class "Default")
      (node (ref "U2") (pin "14") (pinfunction "14_14") (pintype "unspecified"))
    )
    (net (code "110") (name "unconnected-(U2-Pad15)") (class "Default")
      (node (ref "U2") (pin "15") (pinfunction "15_15") (pintype "unspecified"))
    )
    (net (code "111") (name "unconnected-(U2-Pad16)") (class "Default")
      (node (ref "U2") (pin "16") (pinfunction "16_16") (pintype "unspecified"))
    )
    (net (code "112") (name "unconnected-(U2-Pad17)") (class "Default")
      (node (ref "U2") (pin "17") (pinfunction "17_17") (pintype "unspecified"))
    )
    (net (code "113") (name "unconnected-(U2-Pad18)") (class "Default")
      (node (ref "U2") (pin "18") (pinfunction "18_18") (pintype "unspecified"))
    )
    (net (code "114") (name "unconnected-(U2-Pad19)") (class "Default")
      (node (ref "U2") (pin "19") (pinfunction "19_19") (pintype "unspecified"))
    )
    (net (code "115") (name "unconnected-(U2-Pad20)") (class "Default")
      (node (ref "U2") (pin "20") (pinfunction "20_20") (pintype "unspecified"))
    )
    (net (code "116") (name "unconnected-(U2-Pad21)") (class "Default")
      (node (ref "U2") (pin "21") (pinfunction "21_21") (pintype "unspecified"))
    )
    (net (code "117") (name "unconnected-(U2-Pad22)") (class "Default")
      (node (ref "U2") (pin "22") (pinfunction "22_22") (pintype "unspecified"))
    )
    (net (code "118") (name "unconnected-(U2-Pad23)") (class "Default")
      (node (ref "U2") (pin "23") (pinfunction "23_23") (pintype "unspecified"))
    )
    (net (code "119") (name "unconnected-(U2-Pad24)") (class "Default")
      (node (ref "U2") (pin "24") (pinfunction "24_24") (pintype "unspecified"))
    )
    (net (code "120") (name "unconnected-(U2-Pad31)") (class "Default")
      (node (ref "U2") (pin "31") (pinfunction "31_31") (pintype "unspecified"))
    )
    (net (code "121") (name "unconnected-(U2-Pad32)") (class "Default")
      (node (ref "U2") (pin "32") (pinfunction "32_32") (pintype "unspecified"))
    )
    (net (code "122") (name "unconnected-(U2-Pad33)") (class "Default")
      (node (ref "U2") (pin "33") (pinfunction "33_33") (pintype "unspecified"))
    )
    (net (code "123") (name "unconnected-(U2-Pad34)") (class "Default")
      (node (ref "U2") (pin "34") (pinfunction "34_34") (pintype "unspecified"))
    )
    (net (code "124") (name "unconnected-(U2-Pad35)") (class "Default")
      (node (ref "U2") (pin "35") (pinfunction "35_35") (pintype "unspecified"))
    )
    (net (code "125") (name "unconnected-(U2-Pad36)") (class "Default")
      (node (ref "U2") (pin "36") (pinfunction "36_36") (pintype "unspecified"))
    )
    (net (code "126") (name "unconnected-(U2-Pad37)") (class "Default")
      (node (ref "U2") (pin "37") (pinfunction "37_37") (pintype "unspecified"))
    )
    (net (code "127") (name "unconnected-(U2-Pad38)") (class "Default")
      (node (ref "U2") (pin "38") (pinfunction "38_38") (pintype "unspecified"))
    )
    (net (code "128") (name "unconnected-(U2-Pad39)") (class "Default")
      (node (ref "U2") (pin "39") (pinfunction "39_39") (pintype "unspecified"))
    )
    (net (code "129") (name "unconnected-(U2-Pad40)") (class "Default")
      (node (ref "U2") (pin "40") (pinfunction "40_40") (pintype "unspecified"))
    )
    (net (code "130") (name "unconnected-(U2-Pad41)") (class "Default")
      (node (ref "U2") (pin "41") (pinfunction "41_41") (pintype "unspecified"))
    )
    (net (code "131") (name "unconnected-(U2-Pad42)") (class "Default")
      (node (ref "U2") (pin "42") (pinfunction "42_42") (pintype "unspecified"))
    )
    (net (code "132") (name "unconnected-(U2-Pad43)") (class "Default")
      (node (ref "U2") (pin "43") (pinfunction "43_43") (pintype "unspecified"))
    )
    (net (code "133") (name "unconnected-(U2-Pad44)") (class "Default")
      (node (ref "U2") (pin "44") (pinfunction "44_44") (pintype "unspecified"))
    )
    (net (code "134") (name "unconnected-(U2-Pad45)") (class "Default")
      (node (ref "U2") (pin "45") (pinfunction "45_45") (pintype "unspecified"))
    )
    (net (code "135") (name "unconnected-(U2-Pad46)") (class "Default")
      (node (ref "U2") (pin "46") (pinfunction "46_46") (pintype "unspecified"))
    )
    (net (code "136") (name "unconnected-(U2-Pad47)") (class "Default")
      (node (ref "U2") (pin "47") (pinfunction "47_47") (pintype "unspecified"))
    )
    (net (code "137") (name "unconnected-(U2-Pad48)") (class "Default")
      (node (ref "U2") (pin "48") (pinfunction "48_48") (pintype "unspecified"))
    )
    (net (code "138") (name "unconnected-(U2-Pad49)") (class "Default")
      (node (ref "U2") (pin "49") (pinfunction "49_49") (pintype "unspecified"))
    )
    (net (code "139") (name "unconnected-(U2-Pad50)") (class "Default")
      (node (ref "U2") (pin "50") (pinfunction "50_50") (pintype "unspecified"))
    )
    (net (code "140") (name "unconnected-(U2-Pad51)") (class "Default")
      (node (ref "U2") (pin "51") (pinfunction "51_51") (pintype "unspecified"))
    )
    (net (code "141") (name "unconnected-(U2-Pad52)") (class "Default")
      (node (ref "U2") (pin "52") (pinfunction "52_52") (pintype "unspecified"))
    )
    (net (code "142") (name "unconnected-(U3-0-Pad1)") (class "Default")
      (node (ref "U3") (pin "1") (pinfunction "0_1") (pintype "unspecified"))
    )
    (net (code "143") (name "unconnected-(U3-1-Pad2)") (class "Default")
      (node (ref "U3") (pin "2") (pinfunction "1_2") (pintype "unspecified"))
    )
    (net (code "144") (name "unconnected-(U3-2-Pad4)") (class "Default")
      (node (ref "U3") (pin "4") (pinfunction "2_4") (pintype "unspecified"))
    )
    (net (code "145") (name "unconnected-(U3-3-Pad5)") (class "Default")
      (node (ref "U3") (pin "5") (pinfunction "3_5") (pintype "unspecified"))
    )
    (net (code "146") (name "unconnected-(U3-3.3en-Pad24)") (class "Default")
      (node (ref "U3") (pin "24") (pinfunction "3.3en_24") (pintype "unspecified"))
    )
    (net (code "147") (name "unconnected-(U3-6-Pad9)") (class "Default")
      (node (ref "U3") (pin "9") (pinfunction "6_9") (pintype "unspecified"))
    )
    (net (code "148") (name "unconnected-(U3-9-Pad12)") (class "Default")
      (node (ref "U3") (pin "12") (pinfunction "9_12") (pintype "unspecified"))
    )
    (net (code "149") (name "unconnected-(U3-21-Pad34)") (class "Default")
      (node (ref "U3") (pin "34") (pinfunction "21_34") (pintype "unspecified"))
    )
    (net (code "150") (name "unconnected-(U3-22-Pad32)") (class "Default")
      (node (ref "U3") (pin "32") (pinfunction "22_32") (pintype "unspecified"))
    )
    (net (code "151") (name "unconnected-(U3-26-Pad30)") (class "Default")
      (node (ref "U3") (pin "30") (pinfunction "26_30") (pintype "unspecified"))
    )
    (net (code "152") (name "unconnected-(U3-27-Pad29)") (class "Default")
      (node (ref "U3") (pin "29") (pinfunction "27_29") (pintype "unspecified"))
    )
    (net (code "153") (name "unconnected-(U3-28-Pad27)") (class "Default")
      (node (ref "U3") (pin "27") (pinfunction "28_27") (pintype "unspecified"))
    )
    (net (code "154") (name "unconnected-(U3-Pad41)") (class "Default")
      (node (ref "U3") (pin "41") (pinfunction "41_41") (pintype "unspecified"))
    )
    (net (code "155") (name "unconnected-(U3-Pad42)") (class "Default")
      (node (ref "U3") (pin "42") (pinfunction "42_42") (pintype "unspecified"))
    )
    (net (code "156") (name "unconnected-(U3-Pad43)") (class "Default")
      (node (ref "U3") (pin "43") (pinfunction "43_43") (pintype "unspecified"))
    )
    (net (code "157") (name "unconnected-(U3-adc-Pad26)") (class "Default")
      (node (ref "U3") (pin "26") (pinfunction "adc_26") (pintype "unspecified"))
    )
    (net (code "158") (name "unconnected-(U3-vsy-Pad22)") (class "Default")
      (node (ref "U3") (pin "22") (pinfunction "vsy_22") (pintype "unspecified"))
    )
    (net (code "159") (name "unconnected-(U6-EFET-Pad9)") (class "Default")
      (node (ref "U6") (pin "9") (pinfunction "EFET_9") (pintype "unspecified+no_connect"))
    )
  )
)
